# IOexpander.net
KiCad netlist of a schematic drawn in Altium Designer
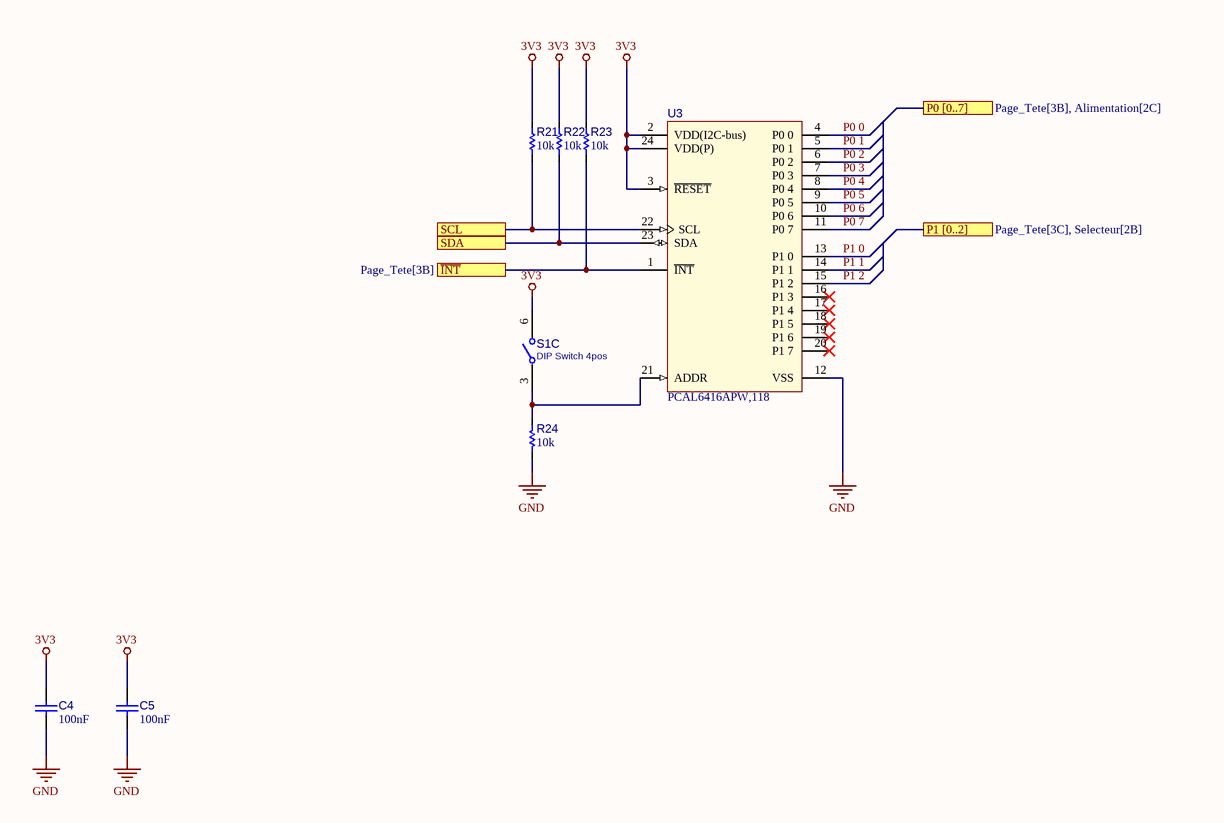
[diagram p0: IOexpander.SchDoc]

(export (version "E")
  (design (tool "Eeschema 10.0.6"))
  (components
    (comp (ref "C4")
      (value "100nF")
      (footprint "C_1608[0603]")
      (description "Capacitor type 1")
      (fields (field (name "TOLERANCE") "10%") (field (name "Comment") "CAP CER 100nF 50V 0603"))
      (libsource (lib "TEP-AltiumLib-Passives-RLC") (part "capacitor"))
    )
    (comp (ref "C5")
      (value "100nF")
      (footprint "C_1608[0603]")
      (description "Capacitor type 1")
      (fields (field (name "TOLERANCE") "10%") (field (name "Comment") "CAP CER 100nF 50V 0603"))
      (libsource (lib "TEP-AltiumLib-Passives-RLC") (part "capacitor"))
    )
    (comp (ref "R21")
      (value "10k")
      (footprint "R_1608[0603]")
      (description "Resistor type 1")
      (fields (field (name "TOLERANCE") "1%") (field (name "Comment") "Res 10k 1% 0603"))
      (libsource (lib "TEP-AltiumLib-Passives-RLC") (part "resistor"))
    )
    (comp (ref "R22")
      (value "10k")
      (footprint "R_1608[0603]")
      (description "Resistor type 1")
      (fields (field (name "TOLERANCE") "1%") (field (name "Comment") "Res 10k 1% 0603"))
      (libsource (lib "TEP-AltiumLib-Passives-RLC") (part "resistor"))
    )
    (comp (ref "R23")
      (value "10k")
      (footprint "R_1608[0603]")
      (description "Resistor type 1")
      (fields (field (name "TOLERANCE") "1%") (field (name "Comment") "Res 10k 1% 0603"))
      (libsource (lib "TEP-AltiumLib-Passives-RLC") (part "resistor"))
    )
    (comp (ref "R24")
      (value "10k")
      (footprint "R_1608[0603]")
      (description "Resistor type 1")
      (fields (field (name "TOLERANCE") "1%") (field (name "Comment") "Res 10k 1% 0603"))
      (libsource (lib "TEP-AltiumLib-Passives-RLC") (part "resistor"))
    )
    (comp (ref "S1")
      (value "DIP Switch 4pos")
      (footprint "S_DIP_SWITCH_50MIL_4POS")
      (description "SWITCH DIP SLIDE SPST 25MA 24V, pitch 1.27mm, height 1.55mm")
      (fields (field (name "Comment") "DSHP04TSGER"))
      (libsource (lib "TEP-AltiumLib") (part "SW_DIP_50MIL_4POS"))
    )
    (comp (ref "U3")
      (value "PCAL6416APW,118")
      (footprint "U_TSSOP24_SOT355-1-IPC_B")
      (description "IC I/O EXPANDER 16BIT 24TSSOP")
      (libsource (lib "TEP-AltiumLib-ICs") (part "U_PCAL6416APW"))
    )
  )
  (nets
    (net (code "1") (name "/P0 0") (class "Default")
      (node (ref "U3") (pin "4") (pinfunction "P0_0_4") (pintype "passive"))
    )
    (net (code "2") (name "/P0 1") (class "Default")
      (node (ref "U3") (pin "5") (pinfunction "P0_1_5") (pintype "passive"))
    )
    (net (code "3") (name "/P0 2") (class "Default")
      (node (ref "U3") (pin "6") (pinfunction "P0_2_6") (pintype "passive"))
    )
    (net (code "4") (name "/P0 3") (class "Default")
      (node (ref "U3") (pin "7") (pinfunction "P0_3_7") (pintype "passive"))
    )
    (net (code "5") (name "/P0 4") (class "Default")
      (node (ref "U3") (pin "8") (pinfunction "P0_4_8") (pintype "passive"))
    )
    (net (code "6") (name "/P0 5") (class "Default")
      (node (ref "U3") (pin "9") (pinfunction "P0_5_9") (pintype "passive"))
    )
    (net (code "7") (name "/P0 6") (class "Default")
      (node (ref "U3") (pin "10") (pinfunction "P0_6_10") (pintype "passive"))
    )
    (net (code "8") (name "/P0 7") (class "Default")
      (node (ref "U3") (pin "11") (pinfunction "P0_7_11") (pintype "passive"))
    )
    (net (code "10") (name "/P1 0") (class "Default")
      (node (ref "U3") (pin "13") (pinfunction "P1_0_13") (pintype "passive"))
    )
    (net (code "11") (name "/P1 1") (class "Default")
      (node (ref "U3") (pin "14") (pinfunction "P1_1_14") (pintype "passive"))
    )
    (net (code "12") (name "/P1 2") (class "Default")
      (node (ref "U3") (pin "15") (pinfunction "P1_2_15") (pintype "passive"))
    )
    (net (code "14") (name "/SCL") (class "Default")
      (node (ref "R21") (pin "1") (pinfunction "1_1") (pintype "passive"))
      (node (ref "U3") (pin "22") (pinfunction "SCL_22") (pintype "input"))
    )
    (net (code "15") (name "/SDA") (class "Default")
      (node (ref "R22") (pin "1") (pinfunction "1_1") (pintype "passive"))
      (node (ref "U3") (pin "23") (pinfunction "SDA_23") (pintype "bidirectional"))
    )
    (net (code "16") (name "/~{INT}") (class "Default")
      (node (ref "R23") (pin "1") (pinfunction "1_1") (pintype "passive"))
      (node (ref "U3") (pin "1") (pinfunction "~{INT}_1") (pintype "open_collector"))
    )
    (net (code "17") (name "3V3") (class "Default")
      (node (ref "C4") (pin "2") (pinfunction "2_2") (pintype "passive"))
      (node (ref "C5") (pin "2") (pinfunction "2_2") (pintype "passive"))
      (node (ref "R21") (pin "2") (pinfunction "2_2") (pintype "passive"))
      (node (ref "R22") (pin "2") (pinfunction "2_2") (pintype "passive"))
      (node (ref "R23") (pin "2") (pinfunction "2_2") (pintype "passive"))
      (node (ref "S1") (pin "6") (pinfunction "6_6") (pintype "passive"))
      (node (ref "U3") (pin "2") (pinfunction "VDD(I2C-bus)_2") (pintype "power_in"))
      (node (ref "U3") (pin "24") (pinfunction "VDD(P)_24") (pintype "power_in"))
      (node (ref "U3") (pin "3") (pinfunction "~{RESET}_3") (pintype "input"))
    )
    (net (code "18") (name "GND") (class "Default")
      (node (ref "C4") (pin "1") (pinfunction "1_1") (pintype "passive"))
      (node (ref "C5") (pin "1") (pinfunction "1_1") (pintype "passive"))
      (node (ref "R24") (pin "1") (pinfunction "1_1") (pintype "passive"))
      (node (ref "U3") (pin "12") (pinfunction "VSS_12") (pintype "power_in"))
    )
    (net (code "19") (name "Net-(U3-ADDR)") (class "Default")
      (node (ref "R24") (pin "2") (pinfunction "2_2") (pintype "passive"))
      (node (ref "S1") (pin "3") (pinfunction "3_3") (pintype "passive"))
      (node (ref "U3") (pin "21") (pinfunction "ADDR_21") (pintype "input"))
    )
    (net (code "20") (name "unconnected-(U3-P1_3-Pad16)") (class "Default")
      (node (ref "U3") (pin "16") (pinfunction "P1_3_16") (pintype "passive+no_connect"))
    )
    (net (code "21") (name "unconnected-(U3-P1_4-Pad17)") (class "Default")
      (node (ref "U3") (pin "17") (pinfunction "P1_4_17") (pintype "passive+no_connect"))
    )
    (net (code "22") (name "unconnected-(U3-P1_5-Pad18)") (class "Default")
      (node (ref "U3") (pin "18") (pinfunction "P1_5_18") (pintype "passive+no_connect"))
    )
    (net (code "23") (name "unconnected-(U3-P1_6-Pad19)") (class "Default")
      (node (ref "U3") (pin "19") (pinfunction "P1_6_19") (pintype "passive+no_connect"))
    )
    (net (code "24") (name "unconnected-(U3-P1_7-Pad20)") (class "Default")
      (node (ref "U3") (pin "20") (pinfunction "P1_7_20") (pintype "passive+no_connect"))
    )
  )
)
